# ENC28J60_2.net
KiCad netlist of a schematic drawn in EAGLE
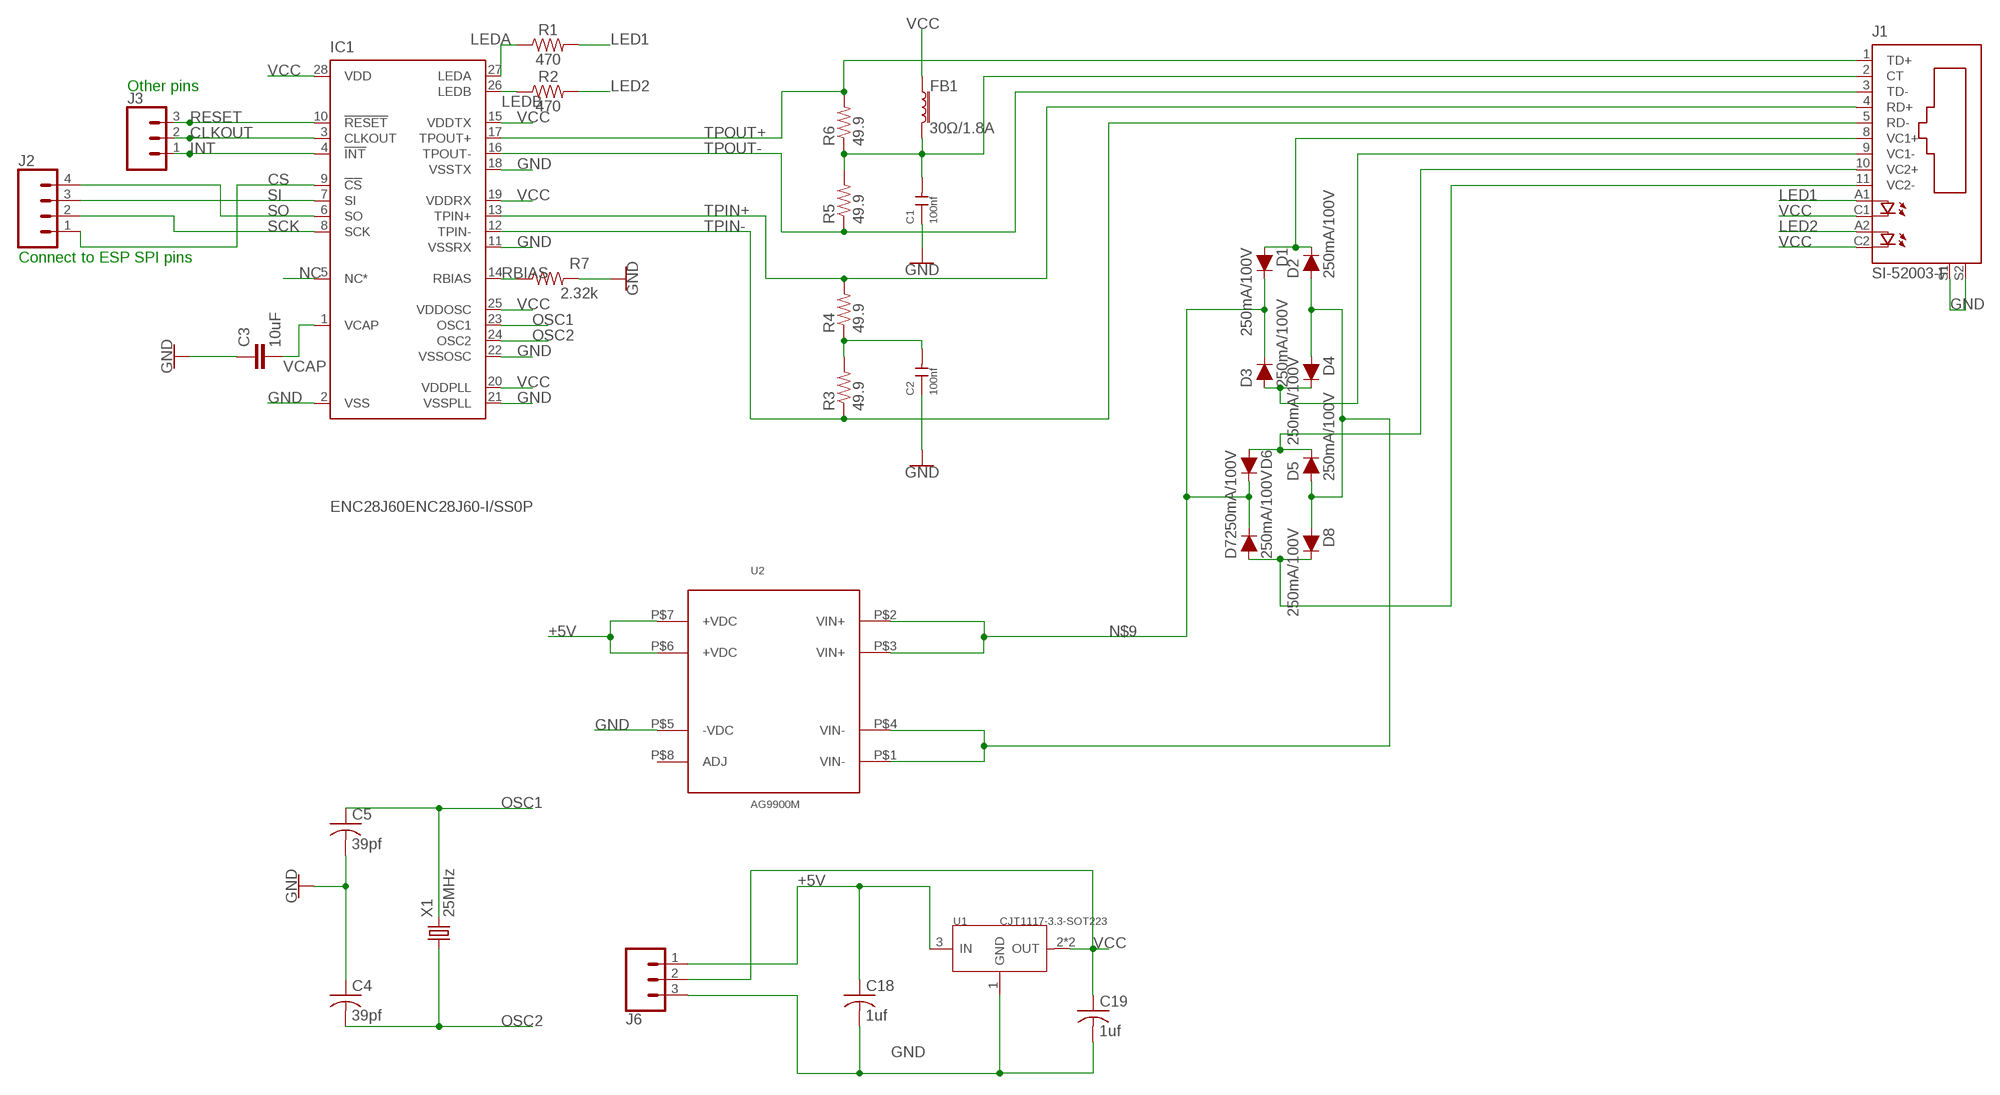
[diagram p0: schematic, sheet 1]

(export (version "E")
  (design (tool "Eeschema 10.0.6"))
  (components
    (comp (ref "C1")
      (value "100nf")
      (footprint "eagle-import:C0603")
      (fields (field (name "MPN") "CC0603KRX7R9BB104"))
      (libsource (lib "eagle-import") (part "CERAMIC-100NF-50V-10%-X7R(0603)"))
    )
    (comp (ref "C2")
      (value "100nf")
      (footprint "eagle-import:C0603")
      (fields (field (name "MPN") "CC0603KRX7R9BB104"))
      (libsource (lib "eagle-import") (part "CERAMIC-100NF-50V-10%-X7R(0603)"))
    )
    (comp (ref "C3")
      (value "10uF")
      (footprint "eagle-import:0805")
      (libsource (lib "eagle-import") (part "10UF-0805-10V-10%"))
    )
    (comp (ref "C4")
      (value "39pf")
      (footprint "eagle-import:C0402")
      (libsource (lib "eagle-import") (part "C-USC0402"))
    )
    (comp (ref "C5")
      (value "39pf")
      (footprint "eagle-import:C0402")
      (libsource (lib "eagle-import") (part "C-USC0402"))
    )
    (comp (ref "C18")
      (value "1uf")
      (footprint "eagle-import:C0402")
      (libsource (lib "eagle-import") (part "C-USC0402"))
    )
    (comp (ref "C19")
      (value "1uf")
      (footprint "eagle-import:C0402")
      (libsource (lib "eagle-import") (part "C-USC0402"))
    )
    (comp (ref "D1")
      (value "250mA/100V")
      (footprint "eagle-import:SOD-323")
      (libsource (lib "eagle-import") (part "DIODE-BAS16J"))
    )
    (comp (ref "D2")
      (value "250mA/100V")
      (footprint "eagle-import:SOD-323")
      (libsource (lib "eagle-import") (part "DIODE-BAS16J"))
    )
    (comp (ref "D3")
      (value "250mA/100V")
      (footprint "eagle-import:SOD-323")
      (libsource (lib "eagle-import") (part "DIODE-BAS16J"))
    )
    (comp (ref "D4")
      (value "250mA/100V")
      (footprint "eagle-import:SOD-323")
      (libsource (lib "eagle-import") (part "DIODE-BAS16J"))
    )
    (comp (ref "D5")
      (value "250mA/100V")
      (footprint "eagle-import:SOD-323")
      (libsource (lib "eagle-import") (part "DIODE-BAS16J"))
    )
    (comp (ref "D6")
      (value "250mA/100V")
      (footprint "eagle-import:SOD-323")
      (libsource (lib "eagle-import") (part "DIODE-BAS16J"))
    )
    (comp (ref "D7")
      (value "250mA/100V")
      (footprint "eagle-import:SOD-323")
      (libsource (lib "eagle-import") (part "DIODE-BAS16J"))
    )
    (comp (ref "D8")
      (value "250mA/100V")
      (footprint "eagle-import:SOD-323")
      (libsource (lib "eagle-import") (part "DIODE-BAS16J"))
    )
    (comp (ref "FB1")
      (value "30Ω/1.8A")
      (footprint "eagle-import:0603")
      (libsource (lib "eagle-import") (part "FERRITE_BEAD-0603"))
    )
    (comp (ref "IC1")
      (value "ENC28J60ENC28J60-I/SS0P")
      (footprint "eagle-import:SOP65P780X200-28")
      (libsource (lib "eagle-import") (part "ENC28J60ENC28J60-I/SS0P"))
    )
    (comp (ref "J1")
      (value "SI-52003-F")
      (footprint "eagle-import:SI-52003-F")
      (fields (field (name "MF") "Stewart Connector"))
      (libsource (lib "eagle-import") (part "SI-52003-F"))
    )
    (comp (ref "J2")
      (value "CONN_04")
      (footprint "eagle-import:1X04")
      (libsource (lib "eagle-import") (part "CONN_04"))
    )
    (comp (ref "J3")
      (value "CONN_03")
      (footprint "eagle-import:1X03")
      (libsource (lib "eagle-import") (part "CONN_03"))
    )
    (comp (ref "J6")
      (value "CONN_03")
      (footprint "eagle-import:1X03")
      (libsource (lib "eagle-import") (part "CONN_03"))
    )
    (comp (ref "R1")
      (value "470")
      (footprint "eagle-import:0603")
      (libsource (lib "eagle-import") (part "470OHM-0603-1/10W-1%"))
    )
    (comp (ref "R2")
      (value "470")
      (footprint "eagle-import:0603")
      (libsource (lib "eagle-import") (part "470OHM-0603-1/10W-1%"))
    )
    (comp (ref "R3")
      (value "49.9")
      (footprint "eagle-import:M0805")
      (libsource (lib "eagle-import") (part "R-US_M0805"))
    )
    (comp (ref "R4")
      (value "49.9")
      (footprint "eagle-import:M0805")
      (libsource (lib "eagle-import") (part "R-US_M0805"))
    )
    (comp (ref "R5")
      (value "49.9")
      (footprint "eagle-import:M0805")
      (libsource (lib "eagle-import") (part "R-US_M0805"))
    )
    (comp (ref "R6")
      (value "49.9")
      (footprint "eagle-import:M0805")
      (libsource (lib "eagle-import") (part "R-US_M0805"))
    )
    (comp (ref "R7")
      (value "2.32k")
      (footprint "eagle-import:0603")
      (libsource (lib "eagle-import") (part "2.2KOHM-0603-1/10W-1%"))
    )
    (comp (ref "U1")
      (value "CJT1117-3.3-SOT223")
      (footprint "eagle-import:SOT-223")
      (fields (field (name "MPN") "CJT1117-3.3"))
      (libsource (lib "eagle-import") (part "PMIC-CJT1117-3.3(SOT223)"))
    )
    (comp (ref "U2")
      (value "AG9900M")
      (footprint "eagle-import:AG9900M_MT")
      (libsource (lib "eagle-import") (part "AG9900M"))
    )
    (comp (ref "X1")
      (value "25MHz")
      (footprint "eagle-import:XTALRR488W48L1067T422H350B")
      (libsource (lib "eagle-import") (part "49S-25-20-2049S-25-20-20"))
    )
  )
  (nets
    (net (code "1") (name "/+5V") (class "Default")
      (node (ref "C18") (pin "1") (pinfunction "1_1") (pintype "passive"))
      (node (ref "J6") (pin "1") (pinfunction "1_1") (pintype "passive"))
      (node (ref "U1") (pin "3") (pinfunction "IN_3") (pintype "bidirectional"))
      (node (ref "U2") (pin "P$6") (pinfunction "+VDC_P$6") (pintype "bidirectional"))
      (node (ref "U2") (pin "P$7") (pinfunction "+VDC_P$7") (pintype "bidirectional"))
    )
    (net (code "2") (name "/CLKOUT") (class "Default")
      (node (ref "IC1") (pin "3") (pinfunction "CLKOUT_3") (pintype "output"))
      (node (ref "J3") (pin "2") (pinfunction "2_2") (pintype "passive"))
    )
    (net (code "3") (name "/CS") (class "Default")
      (node (ref "IC1") (pin "9") (pinfunction "~{CS}_9") (pintype "input"))
      (node (ref "J2") (pin "1") (pinfunction "1_1") (pintype "passive"))
    )
    (net (code "4") (name "/INT") (class "Default")
      (node (ref "IC1") (pin "4") (pinfunction "~{INT}_4") (pintype "output"))
      (node (ref "J3") (pin "1") (pinfunction "1_1") (pintype "passive"))
    )
    (net (code "5") (name "/LED1") (class "Default")
      (node (ref "J1") (pin "A1") (pinfunction "A1_A1") (pintype "passive"))
      (node (ref "R1") (pin "2") (pinfunction "2_2") (pintype "passive"))
    )
    (net (code "6") (name "/LED2") (class "Default")
      (node (ref "J1") (pin "A2") (pinfunction "A2_A2") (pintype "passive"))
      (node (ref "R2") (pin "2") (pinfunction "2_2") (pintype "passive"))
    )
    (net (code "7") (name "/LEDA") (class "Default")
      (node (ref "IC1") (pin "27") (pinfunction "LEDA_27") (pintype "output"))
      (node (ref "R1") (pin "1") (pinfunction "1_1") (pintype "passive"))
    )
    (net (code "8") (name "/LEDB") (class "Default")
      (node (ref "IC1") (pin "26") (pinfunction "LEDB_26") (pintype "output"))
      (node (ref "R2") (pin "1") (pinfunction "1_1") (pintype "passive"))
    )
    (net (code "9") (name "/N$9") (class "Default")
      (node (ref "D1") (pin "C") (pinfunction "C_C") (pintype "passive"))
      (node (ref "D3") (pin "C") (pinfunction "C_C") (pintype "passive"))
      (node (ref "D6") (pin "C") (pinfunction "C_C") (pintype "passive"))
      (node (ref "D7") (pin "C") (pinfunction "C_C") (pintype "passive"))
      (node (ref "U2") (pin "P$2") (pinfunction "VIN+_P$2") (pintype "bidirectional"))
      (node (ref "U2") (pin "P$3") (pinfunction "VIN+_P$3") (pintype "bidirectional"))
    )
    (net (code "10") (name "/NC") (class "Default")
      (node (ref "IC1") (pin "5") (pinfunction "NC*_5") (pintype "output"))
    )
    (net (code "11") (name "/OSC1") (class "Default")
      (node (ref "C5") (pin "1") (pinfunction "1_1") (pintype "passive"))
      (node (ref "IC1") (pin "23") (pinfunction "OSC1_23") (pintype "input"))
      (node (ref "X1") (pin "2") (pinfunction "2_2") (pintype "passive"))
    )
    (net (code "12") (name "/OSC2") (class "Default")
      (node (ref "C4") (pin "2") (pinfunction "2_2") (pintype "passive"))
      (node (ref "IC1") (pin "24") (pinfunction "OSC2_24") (pintype "output"))
      (node (ref "X1") (pin "1") (pinfunction "1_1") (pintype "passive"))
    )
    (net (code "13") (name "/RBIAS") (class "Default")
      (node (ref "IC1") (pin "14") (pinfunction "RBIAS_14") (pintype "input"))
      (node (ref "R7") (pin "1") (pinfunction "1_1") (pintype "passive"))
    )
    (net (code "14") (name "/RESET") (class "Default")
      (node (ref "IC1") (pin "10") (pinfunction "~{RESET}_10") (pintype "input"))
      (node (ref "J3") (pin "3") (pinfunction "3_3") (pintype "passive"))
    )
    (net (code "15") (name "/SCK") (class "Default")
      (node (ref "IC1") (pin "8") (pinfunction "SCK_8") (pintype "input"))
      (node (ref "J2") (pin "2") (pinfunction "2_2") (pintype "passive"))
    )
    (net (code "16") (name "/SI") (class "Default")
      (node (ref "IC1") (pin "7") (pinfunction "SI_7") (pintype "input"))
      (node (ref "J2") (pin "3") (pinfunction "3_3") (pintype "passive"))
    )
    (net (code "17") (name "/SO") (class "Default")
      (node (ref "IC1") (pin "6") (pinfunction "SO_6") (pintype "output"))
      (node (ref "J2") (pin "4") (pinfunction "4_4") (pintype "passive"))
    )
    (net (code "18") (name "/TPIN+") (class "Default")
      (node (ref "IC1") (pin "13") (pinfunction "TPIN+_13") (pintype "input"))
      (node (ref "J1") (pin "4") (pinfunction "RD+_4") (pintype "passive"))
      (node (ref "R4") (pin "2") (pinfunction "2_2") (pintype "passive"))
    )
    (net (code "19") (name "/TPIN-") (class "Default")
      (node (ref "IC1") (pin "12") (pinfunction "TPIN-_12") (pintype "input"))
      (node (ref "J1") (pin "5") (pinfunction "RD-_5") (pintype "passive"))
      (node (ref "R3") (pin "1") (pinfunction "1_1") (pintype "passive"))
    )
    (net (code "20") (name "/TPOUT+") (class "Default")
      (node (ref "IC1") (pin "17") (pinfunction "TPOUT+_17") (pintype "output"))
      (node (ref "J1") (pin "1") (pinfunction "TD+_1") (pintype "passive"))
      (node (ref "R6") (pin "2") (pinfunction "2_2") (pintype "passive"))
    )
    (net (code "21") (name "/TPOUT-") (class "Default")
      (node (ref "IC1") (pin "16") (pinfunction "TPOUT-_16") (pintype "output"))
      (node (ref "J1") (pin "3") (pinfunction "TD-_3") (pintype "passive"))
      (node (ref "R5") (pin "1") (pinfunction "1_1") (pintype "passive"))
    )
    (net (code "22") (name "/VCAP") (class "Default")
      (node (ref "C3") (pin "2") (pinfunction "2_2") (pintype "passive"))
      (node (ref "IC1") (pin "1") (pinfunction "VCAP_1") (pintype "input"))
    )
    (net (code "23") (name "/VCC") (class "Default")
      (node (ref "C19") (pin "1") (pinfunction "1_1") (pintype "passive"))
      (node (ref "FB1") (pin "1") (pinfunction "1_1") (pintype "passive"))
      (node (ref "IC1") (pin "15") (pinfunction "VDDTX_15") (pintype "input"))
      (node (ref "IC1") (pin "19") (pinfunction "VDDRX_19") (pintype "input"))
      (node (ref "IC1") (pin "20") (pinfunction "VDDPLL_20") (pintype "input"))
      (node (ref "IC1") (pin "25") (pinfunction "VDDOSC_25") (pintype "input"))
      (node (ref "IC1") (pin "28") (pinfunction "VDD_28") (pintype "input"))
      (node (ref "J1") (pin "C1") (pinfunction "C1_C1") (pintype "passive"))
      (node (ref "J1") (pin "C2") (pinfunction "C2_C2") (pintype "passive"))
      (node (ref "J6") (pin "2") (pinfunction "2_2") (pintype "passive"))
      (node (ref "U1") (pin "2") (pinfunction "OUT_2") (pintype "bidirectional"))
      (node (ref "U1") (pin "TER") (pinfunction "OUT_TER") (pintype "bidirectional"))
    )
    (net (code "24") (name "GND") (class "Default")
      (node (ref "C1") (pin "1") (pinfunction "1_1") (pintype "passive"))
      (node (ref "C18") (pin "2") (pinfunction "2_2") (pintype "passive"))
      (node (ref "C19") (pin "2") (pinfunction "2_2") (pintype "passive"))
      (node (ref "C2") (pin "1") (pinfunction "1_1") (pintype "passive"))
      (node (ref "C3") (pin "1") (pinfunction "1_1") (pintype "passive"))
      (node (ref "C4") (pin "1") (pinfunction "1_1") (pintype "passive"))
      (node (ref "C5") (pin "2") (pinfunction "2_2") (pintype "passive"))
      (node (ref "IC1") (pin "11") (pinfunction "VSSRX_11") (pintype "input"))
      (node (ref "IC1") (pin "18") (pinfunction "VSSTX_18") (pintype "input"))
      (node (ref "IC1") (pin "2") (pinfunction "VSS_2") (pintype "input"))
      (node (ref "IC1") (pin "21") (pinfunction "VSSPLL_21") (pintype "input"))
      (node (ref "IC1") (pin "22") (pinfunction "VSSOSC_22") (pintype "input"))
      (node (ref "J1") (pin "S1") (pinfunction "S1_S1") (pintype "passive"))
      (node (ref "J1") (pin "S2") (pinfunction "S2_S2") (pintype "passive"))
      (node (ref "J6") (pin "3") (pinfunction "3_3") (pintype "passive"))
      (node (ref "R7") (pin "2") (pinfunction "2_2") (pintype "passive"))
      (node (ref "U1") (pin "1") (pinfunction "GND_1") (pintype "bidirectional"))
      (node (ref "U2") (pin "P$5") (pinfunction "-VDC_P$5") (pintype "bidirectional"))
    )
    (net (code "25") (name "Net-(C2-Pad2)") (class "Default")
      (node (ref "C2") (pin "2") (pinfunction "2_2") (pintype "passive"))
      (node (ref "R3") (pin "2") (pinfunction "2_2") (pintype "passive"))
      (node (ref "R4") (pin "1") (pinfunction "1_1") (pintype "passive"))
    )
    (net (code "26") (name "Net-(D2-PadA)") (class "Default")
      (node (ref "D2") (pin "A") (pinfunction "A_A") (pintype "passive"))
      (node (ref "D4") (pin "A") (pinfunction "A_A") (pintype "passive"))
      (node (ref "D5") (pin "A") (pinfunction "A_A") (pintype "passive"))
      (node (ref "D8") (pin "A") (pinfunction "A_A") (pintype "passive"))
      (node (ref "U2") (pin "P$1") (pinfunction "VIN-_P$1") (pintype "bidirectional"))
      (node (ref "U2") (pin "P$4") (pinfunction "VIN-_P$4") (pintype "bidirectional"))
    )
    (net (code "27") (name "Net-(J1-CT)") (class "Default")
      (node (ref "C1") (pin "2") (pinfunction "2_2") (pintype "passive"))
      (node (ref "FB1") (pin "2") (pinfunction "2_2") (pintype "passive"))
      (node (ref "J1") (pin "2") (pinfunction "CT_2") (pintype "passive"))
      (node (ref "R5") (pin "2") (pinfunction "2_2") (pintype "passive"))
      (node (ref "R6") (pin "1") (pinfunction "1_1") (pintype "passive"))
    )
    (net (code "28") (name "Net-(J1-VC1+)") (class "Default")
      (node (ref "D1") (pin "A") (pinfunction "A_A") (pintype "passive"))
      (node (ref "D2") (pin "C") (pinfunction "C_C") (pintype "passive"))
      (node (ref "J1") (pin "8") (pinfunction "VC1+_8") (pintype "passive"))
    )
    (net (code "29") (name "Net-(J1-VC1-)") (class "Default")
      (node (ref "D3") (pin "A") (pinfunction "A_A") (pintype "passive"))
      (node (ref "D4") (pin "C") (pinfunction "C_C") (pintype "passive"))
      (node (ref "J1") (pin "9") (pinfunction "VC1-_9") (pintype "passive"))
    )
    (net (code "30") (name "Net-(J1-VC2+)") (class "Default")
      (node (ref "D5") (pin "C") (pinfunction "C_C") (pintype "passive"))
      (node (ref "D6") (pin "A") (pinfunction "A_A") (pintype "passive"))
      (node (ref "J1") (pin "10") (pinfunction "VC2+_10") (pintype "passive"))
    )
    (net (code "31") (name "Net-(J1-VC2-)") (class "Default")
      (node (ref "D7") (pin "A") (pinfunction "A_A") (pintype "passive"))
      (node (ref "D8") (pin "C") (pinfunction "C_C") (pintype "passive"))
      (node (ref "J1") (pin "11") (pinfunction "VC2-_11") (pintype "bidirectional"))
    )
    (net (code "32") (name "unconnected-(U2-ADJ-PadP$8)") (class "Default")
      (node (ref "U2") (pin "P$8") (pinfunction "ADJ_P$8") (pintype "bidirectional"))
    )
  )
)
